# Arduino_PLC.net
KiCad netlist of a schematic drawn in EAGLE
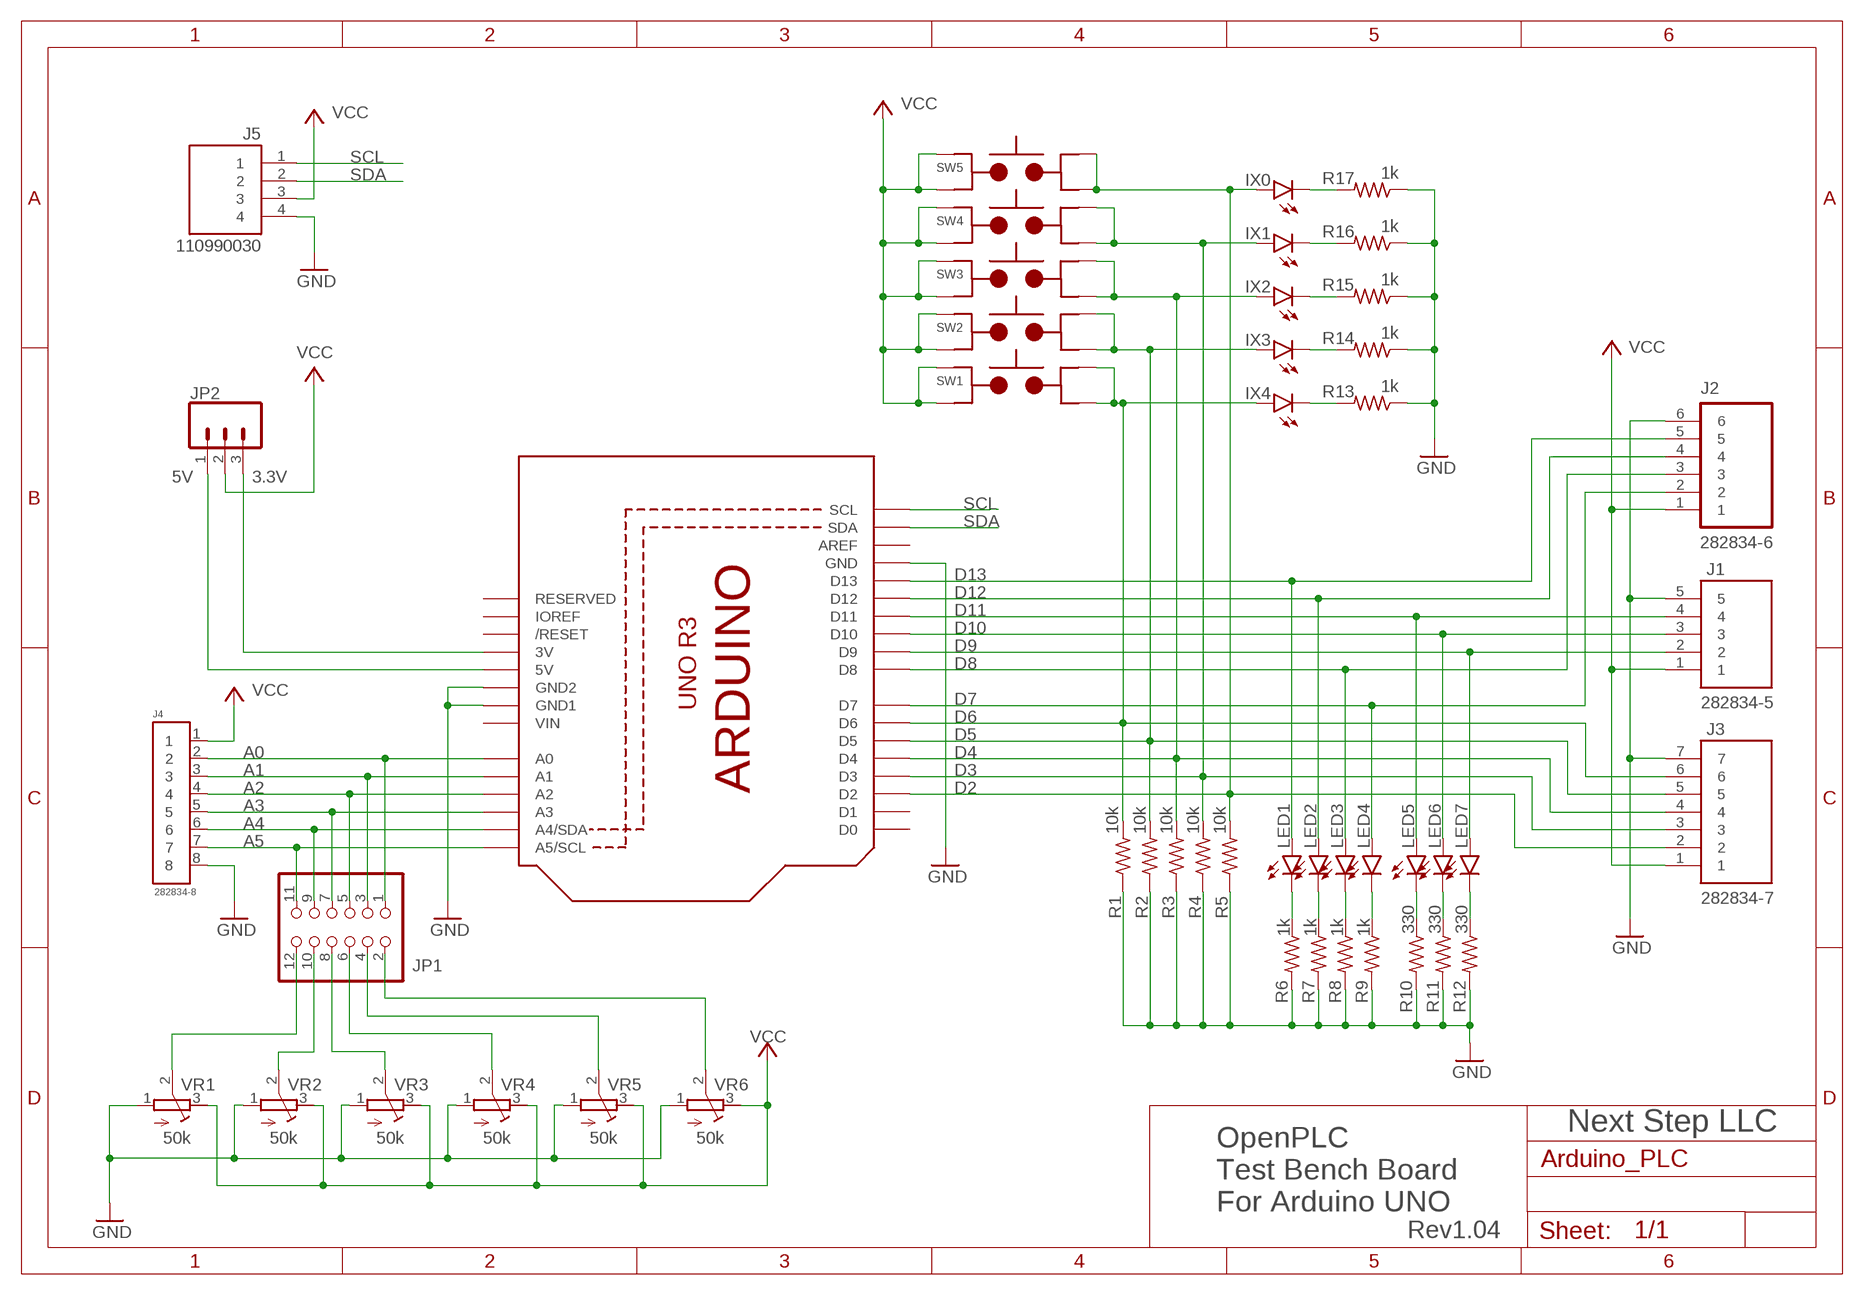
[diagram p0: schematic, sheet 1]

(export (version "E")
  (design (tool "Eeschema 10.0.6"))
  (components
    (comp (ref "IX0")
      (value "LEDCHIP-LED0603")
      (footprint "eagle-import:CHIP-LED0603")
      (libsource (lib "eagle-import") (part "LEDCHIP-LED0603"))
    )
    (comp (ref "IX1")
      (value "LEDCHIP-LED0603")
      (footprint "eagle-import:CHIP-LED0603")
      (libsource (lib "eagle-import") (part "LEDCHIP-LED0603"))
    )
    (comp (ref "IX2")
      (value "LEDCHIP-LED0603")
      (footprint "eagle-import:CHIP-LED0603")
      (libsource (lib "eagle-import") (part "LEDCHIP-LED0603"))
    )
    (comp (ref "IX3")
      (value "LEDCHIP-LED0603")
      (footprint "eagle-import:CHIP-LED0603")
      (libsource (lib "eagle-import") (part "LEDCHIP-LED0603"))
    )
    (comp (ref "IX4")
      (value "LEDCHIP-LED0603")
      (footprint "eagle-import:CHIP-LED0603")
      (libsource (lib "eagle-import") (part "LEDCHIP-LED0603"))
    )
    (comp (ref "J1")
      (value "282834-5")
      (footprint "eagle-import:TE_282834-5")
      (fields (field (name "MF") "TE Connectivity"))
      (libsource (lib "eagle-import") (part "282834-5"))
    )
    (comp (ref "J2")
      (value "282834-6")
      (footprint "eagle-import:TE_282834-6")
      (fields (field (name "MF") "TE Connectivity"))
      (libsource (lib "eagle-import") (part "282834-6"))
    )
    (comp (ref "J3")
      (value "282834-7")
      (footprint "eagle-import:TE_282834-7")
      (fields (field (name "MF") "TE Connectivity"))
      (libsource (lib "eagle-import") (part "282834-7"))
    )
    (comp (ref "J4")
      (value "282834-8")
      (footprint "eagle-import:HDRV8W85P254_8X1_2078X650X1000")
      (fields (field (name "MF") "TE Connectivity"))
      (libsource (lib "eagle-import") (part "282834-8"))
    )
    (comp (ref "J5")
      (value "110990030")
      (footprint "eagle-import:SEEED_110990030")
      (fields (field (name "MF") "Seeed Technology Co., Ltd"))
      (libsource (lib "eagle-import") (part "110990030"))
    )
    (comp (ref "JP1")
      (value "PINHD-2X6")
      (footprint "eagle-import:2X06")
      (libsource (lib "eagle-import") (part "PINHD-2X6"))
    )
    (comp (ref "JP2")
      (value "455-1750-1-ND")
      (footprint "eagle-import:1X03")
      (libsource (lib "eagle-import") (part "CONN_03"))
    )
    (comp (ref "LED1")
      (value "LEDCHIP-LED0603")
      (footprint "eagle-import:CHIP-LED0603")
      (libsource (lib "eagle-import") (part "LEDCHIP-LED0603"))
    )
    (comp (ref "LED2")
      (value "LEDCHIP-LED0603")
      (footprint "eagle-import:CHIP-LED0603")
      (libsource (lib "eagle-import") (part "LEDCHIP-LED0603"))
    )
    (comp (ref "LED3")
      (value "LEDCHIP-LED0603")
      (footprint "eagle-import:CHIP-LED0603")
      (libsource (lib "eagle-import") (part "LEDCHIP-LED0603"))
    )
    (comp (ref "LED4")
      (value "LEDCHIP-LED0603")
      (footprint "eagle-import:CHIP-LED0603")
      (libsource (lib "eagle-import") (part "LEDCHIP-LED0603"))
    )
    (comp (ref "LED5")
      (value "LEDCHIP-LED0603")
      (footprint "eagle-import:CHIP-LED0603")
      (libsource (lib "eagle-import") (part "LEDCHIP-LED0603"))
    )
    (comp (ref "LED6")
      (value "LEDCHIP-LED0603")
      (footprint "eagle-import:CHIP-LED0603")
      (libsource (lib "eagle-import") (part "LEDCHIP-LED0603"))
    )
    (comp (ref "LED7")
      (value "LEDCHIP-LED0603")
      (footprint "eagle-import:CHIP-LED0603")
      (libsource (lib "eagle-import") (part "LEDCHIP-LED0603"))
    )
    (comp (ref "R1")
      (value "10k")
      (footprint "eagle-import:R0603")
      (libsource (lib "eagle-import") (part "R-US_R0603"))
    )
    (comp (ref "R2")
      (value "10k")
      (footprint "eagle-import:R0603")
      (libsource (lib "eagle-import") (part "R-US_R0603"))
    )
    (comp (ref "R3")
      (value "10k")
      (footprint "eagle-import:R0603")
      (libsource (lib "eagle-import") (part "R-US_R0603"))
    )
    (comp (ref "R4")
      (value "10k")
      (footprint "eagle-import:R0603")
      (libsource (lib "eagle-import") (part "R-US_R0603"))
    )
    (comp (ref "R5")
      (value "10k")
      (footprint "eagle-import:R0603")
      (libsource (lib "eagle-import") (part "R-US_R0603"))
    )
    (comp (ref "R6")
      (value "1k")
      (footprint "eagle-import:R0603")
      (libsource (lib "eagle-import") (part "R-US_R0603"))
    )
    (comp (ref "R7")
      (value "1k")
      (footprint "eagle-import:R0603")
      (libsource (lib "eagle-import") (part "R-US_R0603"))
    )
    (comp (ref "R8")
      (value "1k")
      (footprint "eagle-import:R0603")
      (libsource (lib "eagle-import") (part "R-US_R0603"))
    )
    (comp (ref "R9")
      (value "1k")
      (footprint "eagle-import:R0603")
      (libsource (lib "eagle-import") (part "R-US_R0603"))
    )
    (comp (ref "R10")
      (value "330")
      (footprint "eagle-import:R0603")
      (libsource (lib "eagle-import") (part "R-US_R0603"))
    )
    (comp (ref "R11")
      (value "330")
      (footprint "eagle-import:R0603")
      (libsource (lib "eagle-import") (part "R-US_R0603"))
    )
    (comp (ref "R12")
      (value "330")
      (footprint "eagle-import:R0603")
      (libsource (lib "eagle-import") (part "R-US_R0603"))
    )
    (comp (ref "R13")
      (value "1k")
      (footprint "eagle-import:R0603")
      (libsource (lib "eagle-import") (part "R-US_R0603"))
    )
    (comp (ref "R14")
      (value "1k")
      (footprint "eagle-import:R0603")
      (libsource (lib "eagle-import") (part "R-US_R0603"))
    )
    (comp (ref "R15")
      (value "1k")
      (footprint "eagle-import:R0603")
      (libsource (lib "eagle-import") (part "R-US_R0603"))
    )
    (comp (ref "R16")
      (value "1k")
      (footprint "eagle-import:R0603")
      (libsource (lib "eagle-import") (part "R-US_R0603"))
    )
    (comp (ref "R17")
      (value "1k")
      (footprint "eagle-import:R0603")
      (libsource (lib "eagle-import") (part "R-US_R0603"))
    )
    (comp (ref "SW1")
      (value "TL3342F160QG/TR")
      (footprint "eagle-import:SW_TL3342F160QG_TR")
      (fields (field (name "MF") "E-Switch"))
      (libsource (lib "eagle-import") (part "TL3342F160QG/TR"))
    )
    (comp (ref "SW2")
      (value "TL3342F160QG/TR")
      (footprint "eagle-import:SW_TL3342F160QG_TR")
      (fields (field (name "MF") "E-Switch"))
      (libsource (lib "eagle-import") (part "TL3342F160QG/TR"))
    )
    (comp (ref "SW3")
      (value "TL3342F160QG/TR")
      (footprint "eagle-import:SW_TL3342F160QG_TR")
      (fields (field (name "MF") "E-Switch"))
      (libsource (lib "eagle-import") (part "TL3342F160QG/TR"))
    )
    (comp (ref "SW4")
      (value "TL3342F160QG/TR")
      (footprint "eagle-import:SW_TL3342F160QG_TR")
      (fields (field (name "MF") "E-Switch"))
      (libsource (lib "eagle-import") (part "TL3342F160QG/TR"))
    )
    (comp (ref "SW5")
      (value "TL3342F160QG/TR")
      (footprint "eagle-import:SW_TL3342F160QG_TR")
      (fields (field (name "MF") "E-Switch"))
      (libsource (lib "eagle-import") (part "TL3342F160QG/TR"))
    )
    (comp (ref "U1")
      (value "ARDUINOR3-DIMENSION")
      (footprint "eagle-import:ARDUINOR3")
      (libsource (lib "eagle-import") (part "ARDUINOR3-DIMENSION"))
    )
    (comp (ref "VR1")
      (value "50k")
      (footprint "eagle-import:RTRIM3339P")
      (libsource (lib "eagle-import") (part "R-TRIMM3339P"))
    )
    (comp (ref "VR2")
      (value "50k")
      (footprint "eagle-import:RTRIM3339P")
      (libsource (lib "eagle-import") (part "R-TRIMM3339P"))
    )
    (comp (ref "VR3")
      (value "50k")
      (footprint "eagle-import:RTRIM3339P")
      (libsource (lib "eagle-import") (part "R-TRIMM3339P"))
    )
    (comp (ref "VR4")
      (value "50k")
      (footprint "eagle-import:RTRIM3339P")
      (libsource (lib "eagle-import") (part "R-TRIMM3339P"))
    )
    (comp (ref "VR5")
      (value "50k")
      (footprint "eagle-import:RTRIM3339P")
      (libsource (lib "eagle-import") (part "R-TRIMM3339P"))
    )
    (comp (ref "VR6")
      (value "50k")
      (footprint "eagle-import:RTRIM3339P")
      (libsource (lib "eagle-import") (part "R-TRIMM3339P"))
    )
  )
  (nets
    (net (code "1") (name "/A0") (class "Default")
      (node (ref "J4") (pin "2") (pinfunction "2_2") (pintype "passive"))
      (node (ref "JP1") (pin "1") (pinfunction "1_1") (pintype "passive"))
      (node (ref "U1") (pin "A0") (pinfunction "A0_A0") (pintype "bidirectional"))
    )
    (net (code "2") (name "/A1") (class "Default")
      (node (ref "J4") (pin "3") (pinfunction "3_3") (pintype "passive"))
      (node (ref "JP1") (pin "3") (pinfunction "3_3") (pintype "passive"))
      (node (ref "U1") (pin "A1") (pinfunction "A1_A1") (pintype "bidirectional"))
    )
    (net (code "3") (name "/A2") (class "Default")
      (node (ref "J4") (pin "4") (pinfunction "4_4") (pintype "passive"))
      (node (ref "JP1") (pin "5") (pinfunction "5_5") (pintype "passive"))
      (node (ref "U1") (pin "A2") (pinfunction "A2_A2") (pintype "bidirectional"))
    )
    (net (code "4") (name "/A3") (class "Default")
      (node (ref "J4") (pin "5") (pinfunction "5_5") (pintype "passive"))
      (node (ref "JP1") (pin "7") (pinfunction "7_7") (pintype "passive"))
      (node (ref "U1") (pin "A3") (pinfunction "A3_A3") (pintype "bidirectional"))
    )
    (net (code "5") (name "/A4") (class "Default")
      (node (ref "J4") (pin "6") (pinfunction "6_6") (pintype "passive"))
      (node (ref "JP1") (pin "9") (pinfunction "9_9") (pintype "passive"))
      (node (ref "U1") (pin "A4") (pinfunction "A4/SDA_A4") (pintype "bidirectional"))
    )
    (net (code "6") (name "/A5") (class "Default")
      (node (ref "J4") (pin "7") (pinfunction "7_7") (pintype "passive"))
      (node (ref "JP1") (pin "11") (pinfunction "11_11") (pintype "passive"))
      (node (ref "U1") (pin "A5") (pinfunction "A5/SCL_A5") (pintype "bidirectional"))
    )
    (net (code "7") (name "/D2") (class "Default")
      (node (ref "IX0") (pin "A") (pinfunction "A_A") (pintype "passive"))
      (node (ref "J3") (pin "2") (pinfunction "2_2") (pintype "passive"))
      (node (ref "R5") (pin "2") (pinfunction "2_2") (pintype "passive"))
      (node (ref "SW5") (pin "1") (pinfunction "1_1") (pintype "passive"))
      (node (ref "SW5") (pin "2") (pinfunction "2_2") (pintype "passive"))
      (node (ref "U1") (pin "D2") (pinfunction "D2_D2") (pintype "bidirectional"))
    )
    (net (code "8") (name "/D3") (class "Default")
      (node (ref "IX1") (pin "A") (pinfunction "A_A") (pintype "passive"))
      (node (ref "J3") (pin "3") (pinfunction "3_3") (pintype "passive"))
      (node (ref "R4") (pin "2") (pinfunction "2_2") (pintype "passive"))
      (node (ref "SW4") (pin "1") (pinfunction "1_1") (pintype "passive"))
      (node (ref "SW4") (pin "2") (pinfunction "2_2") (pintype "passive"))
      (node (ref "U1") (pin "D3") (pinfunction "D3_D3") (pintype "bidirectional"))
    )
    (net (code "9") (name "/D4") (class "Default")
      (node (ref "IX2") (pin "A") (pinfunction "A_A") (pintype "passive"))
      (node (ref "J3") (pin "4") (pinfunction "4_4") (pintype "passive"))
      (node (ref "R3") (pin "2") (pinfunction "2_2") (pintype "passive"))
      (node (ref "SW3") (pin "1") (pinfunction "1_1") (pintype "passive"))
      (node (ref "SW3") (pin "2") (pinfunction "2_2") (pintype "passive"))
      (node (ref "U1") (pin "D4") (pinfunction "D4_D4") (pintype "bidirectional"))
    )
    (net (code "10") (name "/D5") (class "Default")
      (node (ref "IX3") (pin "A") (pinfunction "A_A") (pintype "passive"))
      (node (ref "J3") (pin "5") (pinfunction "5_5") (pintype "passive"))
      (node (ref "R2") (pin "2") (pinfunction "2_2") (pintype "passive"))
      (node (ref "SW2") (pin "1") (pinfunction "1_1") (pintype "passive"))
      (node (ref "SW2") (pin "2") (pinfunction "2_2") (pintype "passive"))
      (node (ref "U1") (pin "D5") (pinfunction "D5_D5") (pintype "bidirectional"))
    )
    (net (code "11") (name "/D6") (class "Default")
      (node (ref "IX4") (pin "A") (pinfunction "A_A") (pintype "passive"))
      (node (ref "J3") (pin "6") (pinfunction "6_6") (pintype "passive"))
      (node (ref "R1") (pin "2") (pinfunction "2_2") (pintype "passive"))
      (node (ref "SW1") (pin "1") (pinfunction "1_1") (pintype "passive"))
      (node (ref "SW1") (pin "2") (pinfunction "2_2") (pintype "passive"))
      (node (ref "U1") (pin "D6") (pinfunction "D6_D6") (pintype "bidirectional"))
    )
    (net (code "12") (name "/D7") (class "Default")
      (node (ref "J2") (pin "2") (pinfunction "2_2") (pintype "passive"))
      (node (ref "LED4") (pin "A") (pinfunction "A_A") (pintype "passive"))
      (node (ref "U1") (pin "D7") (pinfunction "D7_D7") (pintype "bidirectional"))
    )
    (net (code "13") (name "/D8") (class "Default")
      (node (ref "J2") (pin "3") (pinfunction "3_3") (pintype "passive"))
      (node (ref "LED3") (pin "A") (pinfunction "A_A") (pintype "passive"))
      (node (ref "U1") (pin "D8") (pinfunction "D8_D8") (pintype "bidirectional"))
    )
    (net (code "14") (name "/D9") (class "Default")
      (node (ref "J1") (pin "2") (pinfunction "2_2") (pintype "passive"))
      (node (ref "LED7") (pin "A") (pinfunction "A_A") (pintype "passive"))
      (node (ref "U1") (pin "D9") (pinfunction "D9_D9") (pintype "bidirectional"))
    )
    (net (code "15") (name "/D10") (class "Default")
      (node (ref "J1") (pin "3") (pinfunction "3_3") (pintype "passive"))
      (node (ref "LED6") (pin "A") (pinfunction "A_A") (pintype "passive"))
      (node (ref "U1") (pin "D10") (pinfunction "D10_D10") (pintype "bidirectional"))
    )
    (net (code "16") (name "/D11") (class "Default")
      (node (ref "J1") (pin "4") (pinfunction "4_4") (pintype "passive"))
      (node (ref "LED5") (pin "A") (pinfunction "A_A") (pintype "passive"))
      (node (ref "U1") (pin "D11") (pinfunction "D11_D11") (pintype "bidirectional"))
    )
    (net (code "17") (name "/D12") (class "Default")
      (node (ref "J2") (pin "4") (pinfunction "4_4") (pintype "passive"))
      (node (ref "LED2") (pin "A") (pinfunction "A_A") (pintype "passive"))
      (node (ref "U1") (pin "D12") (pinfunction "D12_D12") (pintype "bidirectional"))
    )
    (net (code "18") (name "/D13") (class "Default")
      (node (ref "J2") (pin "5") (pinfunction "5_5") (pintype "passive"))
      (node (ref "LED1") (pin "A") (pinfunction "A_A") (pintype "passive"))
      (node (ref "U1") (pin "D13") (pinfunction "D13_D13") (pintype "bidirectional"))
    )
    (net (code "19") (name "/SCL") (class "Default")
      (node (ref "J5") (pin "1") (pinfunction "1_1") (pintype "passive"))
      (node (ref "U1") (pin "SCL") (pinfunction "SCL_SCL") (pintype "bidirectional"))
    )
    (net (code "20") (name "/SDA") (class "Default")
      (node (ref "J5") (pin "2") (pinfunction "2_2") (pintype "passive"))
      (node (ref "U1") (pin "SDA") (pinfunction "SDA_SDA") (pintype "bidirectional"))
    )
    (net (code "21") (name "/VIN") (class "Default")
      (node (ref "U1") (pin "VIN") (pinfunction "VIN_VIN") (pintype "power_in"))
    )
    (net (code "22") (name "GND") (class "Default")
      (node (ref "J1") (pin "5") (pinfunction "5_5") (pintype "passive"))
      (node (ref "J2") (pin "6") (pinfunction "6_6") (pintype "passive"))
      (node (ref "J3") (pin "7") (pinfunction "7_7") (pintype "passive"))
      (node (ref "J4") (pin "8") (pinfunction "8_8") (pintype "passive"))
      (node (ref "J5") (pin "4") (pinfunction "4_4") (pintype "passive"))
      (node (ref "R1") (pin "1") (pinfunction "1_1") (pintype "passive"))
      (node (ref "R10") (pin "2") (pinfunction "2_2") (pintype "passive"))
      (node (ref "R11") (pin "2") (pinfunction "2_2") (pintype "passive"))
      (node (ref "R12") (pin "2") (pinfunction "2_2") (pintype "passive"))
      (node (ref "R13") (pin "1") (pinfunction "1_1") (pintype "passive"))
      (node (ref "R14") (pin "1") (pinfunction "1_1") (pintype "passive"))
      (node (ref "R15") (pin "1") (pinfunction "1_1") (pintype "passive"))
      (node (ref "R16") (pin "1") (pinfunction "1_1") (pintype "passive"))
      (node (ref "R17") (pin "1") (pinfunction "1_1") (pintype "passive"))
      (node (ref "R2") (pin "1") (pinfunction "1_1") (pintype "passive"))
      (node (ref "R3") (pin "1") (pinfunction "1_1") (pintype "passive"))
      (node (ref "R4") (pin "1") (pinfunction "1_1") (pintype "passive"))
      (node (ref "R5") (pin "1") (pinfunction "1_1") (pintype "passive"))
      (node (ref "R6") (pin "2") (pinfunction "2_2") (pintype "passive"))
      (node (ref "R7") (pin "2") (pinfunction "2_2") (pintype "passive"))
      (node (ref "R8") (pin "2") (pinfunction "2_2") (pintype "passive"))
      (node (ref "R9") (pin "2") (pinfunction "2_2") (pintype "passive"))
      (node (ref "U1") (pin "GND") (pinfunction "GND_GND") (pintype "power_in"))
      (node (ref "U1") (pin "GND1") (pinfunction "GND1_GND1") (pintype "power_in"))
      (node (ref "U1") (pin "GND2") (pinfunction "GND2_GND2") (pintype "power_in"))
      (node (ref "VR1") (pin "1") (pinfunction "A_1") (pintype "passive"))
      (node (ref "VR2") (pin "1") (pinfunction "A_1") (pintype "passive"))
      (node (ref "VR3") (pin "1") (pinfunction "A_1") (pintype "passive"))
      (node (ref "VR4") (pin "1") (pinfunction "A_1") (pintype "passive"))
      (node (ref "VR5") (pin "1") (pinfunction "A_1") (pintype "passive"))
      (node (ref "VR6") (pin "1") (pinfunction "A_1") (pintype "passive"))
    )
    (net (code "23") (name "Net-(IX0-PadC)") (class "Default")
      (node (ref "IX0") (pin "C") (pinfunction "C_C") (pintype "passive"))
      (node (ref "R17") (pin "2") (pinfunction "2_2") (pintype "passive"))
    )
    (net (code "24") (name "Net-(IX1-PadC)") (class "Default")
      (node (ref "IX1") (pin "C") (pinfunction "C_C") (pintype "passive"))
      (node (ref "R16") (pin "2") (pinfunction "2_2") (pintype "passive"))
    )
    (net (code "25") (name "Net-(IX2-PadC)") (class "Default")
      (node (ref "IX2") (pin "C") (pinfunction "C_C") (pintype "passive"))
      (node (ref "R15") (pin "2") (pinfunction "2_2") (pintype "passive"))
    )
    (net (code "26") (name "Net-(IX3-PadC)") (class "Default")
      (node (ref "IX3") (pin "C") (pinfunction "C_C") (pintype "passive"))
      (node (ref "R14") (pin "2") (pinfunction "2_2") (pintype "passive"))
    )
    (net (code "27") (name "Net-(IX4-PadC)") (class "Default")
      (node (ref "IX4") (pin "C") (pinfunction "C_C") (pintype "passive"))
      (node (ref "R13") (pin "2") (pinfunction "2_2") (pintype "passive"))
    )
    (net (code "28") (name "Net-(JP2-Pad1)") (class "Default")
      (node (ref "JP2") (pin "1") (pinfunction "1_1") (pintype "passive"))
      (node (ref "U1") (pin "5V") (pinfunction "5V_5V") (pintype "power_in"))
    )
    (net (code "29") (name "Net-(JP2-Pad3)") (class "Default")
      (node (ref "JP2") (pin "3") (pinfunction "3_3") (pintype "passive"))
      (node (ref "U1") (pin "3V") (pinfunction "3V_3V") (pintype "power_in"))
    )
    (net (code "30") (name "Net-(LED1-PadC)") (class "Default")
      (node (ref "LED1") (pin "C") (pinfunction "C_C") (pintype "passive"))
      (node (ref "R6") (pin "1") (pinfunction "1_1") (pintype "passive"))
    )
    (net (code "31") (name "Net-(LED2-PadC)") (class "Default")
      (node (ref "LED2") (pin "C") (pinfunction "C_C") (pintype "passive"))
      (node (ref "R7") (pin "1") (pinfunction "1_1") (pintype "passive"))
    )
    (net (code "32") (name "Net-(LED3-PadC)") (class "Default")
      (node (ref "LED3") (pin "C") (pinfunction "C_C") (pintype "passive"))
      (node (ref "R8") (pin "1") (pinfunction "1_1") (pintype "passive"))
    )
    (net (code "33") (name "Net-(LED4-PadC)") (class "Default")
      (node (ref "LED4") (pin "C") (pinfunction "C_C") (pintype "passive"))
      (node (ref "R9") (pin "1") (pinfunction "1_1") (pintype "passive"))
    )
    (net (code "34") (name "Net-(LED5-PadC)") (class "Default")
      (node (ref "LED5") (pin "C") (pinfunction "C_C") (pintype "passive"))
      (node (ref "R10") (pin "1") (pinfunction "1_1") (pintype "passive"))
    )
    (net (code "35") (name "Net-(LED6-PadC)") (class "Default")
      (node (ref "LED6") (pin "C") (pinfunction "C_C") (pintype "passive"))
      (node (ref "R11") (pin "1") (pinfunction "1_1") (pintype "passive"))
    )
    (net (code "36") (name "Net-(LED7-PadC)") (class "Default")
      (node (ref "LED7") (pin "C") (pinfunction "C_C") (pintype "passive"))
      (node (ref "R12") (pin "1") (pinfunction "1_1") (pintype "passive"))
    )
    (net (code "37") (name "Net-(VR1-S)") (class "Default")
      (node (ref "JP1") (pin "12") (pinfunction "12_12") (pintype "passive"))
      (node (ref "VR1") (pin "2") (pinfunction "S_2") (pintype "passive"))
    )
    (net (code "38") (name "Net-(VR2-S)") (class "Default")
      (node (ref "JP1") (pin "10") (pinfunction "10_10") (pintype "passive"))
      (node (ref "VR2") (pin "2") (pinfunction "S_2") (pintype "passive"))
    )
    (net (code "39") (name "Net-(VR3-S)") (class "Default")
      (node (ref "JP1") (pin "8") (pinfunction "8_8") (pintype "passive"))
      (node (ref "VR3") (pin "2") (pinfunction "S_2") (pintype "passive"))
    )
    (net (code "40") (name "Net-(VR4-S)") (class "Default")
      (node (ref "JP1") (pin "6") (pinfunction "6_6") (pintype "passive"))
      (node (ref "VR4") (pin "2") (pinfunction "S_2") (pintype "passive"))
    )
    (net (code "41") (name "Net-(VR5-S)") (class "Default")
      (node (ref "JP1") (pin "4") (pinfunction "4_4") (pintype "passive"))
      (node (ref "VR5") (pin "2") (pinfunction "S_2") (pintype "passive"))
    )
    (net (code "42") (name "Net-(VR6-S)") (class "Default")
      (node (ref "JP1") (pin "2") (pinfunction "2_2") (pintype "passive"))
      (node (ref "VR6") (pin "2") (pinfunction "S_2") (pintype "passive"))
    )
    (net (code "43") (name "VCC") (class "Default")
      (node (ref "J1") (pin "1") (pinfunction "1_1") (pintype "passive"))
      (node (ref "J2") (pin "1") (pinfunction "1_1") (pintype "passive"))
      (node (ref "J3") (pin "1") (pinfunction "1_1") (pintype "passive"))
      (node (ref "J4") (pin "1") (pinfunction "1_1") (pintype "passive"))
      (node (ref "J5") (pin "3") (pinfunction "3_3") (pintype "passive"))
      (node (ref "JP2") (pin "2") (pinfunction "2_2") (pintype "passive"))
      (node (ref "SW1") (pin "3") (pinfunction "3_3") (pintype "passive"))
      (node (ref "SW1") (pin "4") (pinfunction "4_4") (pintype "passive"))
      (node (ref "SW2") (pin "3") (pinfunction "3_3") (pintype "passive"))
      (node (ref "SW2") (pin "4") (pinfunction "4_4") (pintype "passive"))
      (node (ref "SW3") (pin "3") (pinfunction "3_3") (pintype "passive"))
      (node (ref "SW3") (pin "4") (pinfunction "4_4") (pintype "passive"))
      (node (ref "SW4") (pin "3") (pinfunction "3_3") (pintype "passive"))
      (node (ref "SW4") (pin "4") (pinfunction "4_4") (pintype "passive"))
      (node (ref "SW5") (pin "3") (pinfunction "3_3") (pintype "passive"))
      (node (ref "SW5") (pin "4") (pinfunction "4_4") (pintype "passive"))
      (node (ref "VR1") (pin "3") (pinfunction "E_3") (pintype "passive"))
      (node (ref "VR2") (pin "3") (pinfunction "E_3") (pintype "passive"))
      (node (ref "VR3") (pin "3") (pinfunction "E_3") (pintype "passive"))
      (node (ref "VR4") (pin "3") (pinfunction "E_3") (pintype "passive"))
      (node (ref "VR5") (pin "3") (pinfunction "E_3") (pintype "passive"))
      (node (ref "VR6") (pin "3") (pinfunction "E_3") (pintype "passive"))
    )
    (net (code "44") (name "unconnected-(U1-PadAREF)") (class "Default")
      (node (ref "U1") (pin "AREF") (pinfunction "AREF_AREF") (pintype "bidirectional"))
    )
    (net (code "45") (name "unconnected-(U1-PadD0)") (class "Default")
      (node (ref "U1") (pin "D0") (pinfunction "D0_D0") (pintype "bidirectional"))
    )
    (net (code "46") (name "unconnected-(U1-PadD1)") (class "Default")
      (node (ref "U1") (pin "D1") (pinfunction "D1_D1") (pintype "bidirectional"))
    )
    (net (code "47") (name "unconnected-(U1-PadIOREF)") (class "Default")
      (node (ref "U1") (pin "IOREF") (pinfunction "IOREF_IOREF") (pintype "output"))
    )
    (net (code "48") (name "unconnected-(U1-PadRESERVED)") (class "Default")
      (node (ref "U1") (pin "RESERVED") (pinfunction "RESERVED_RESERVED") (pintype "no_connect"))
    )
    (net (code "49") (name "unconnected-(U1-{slash}RESET-PadRESET)") (class "Default")
      (node (ref "U1") (pin "RESET") (pinfunction "/RESET_RESET") (pintype "bidirectional"))
    )
  )
)
